# pcb.net
KiCad netlist of a schematic drawn in EAGLE
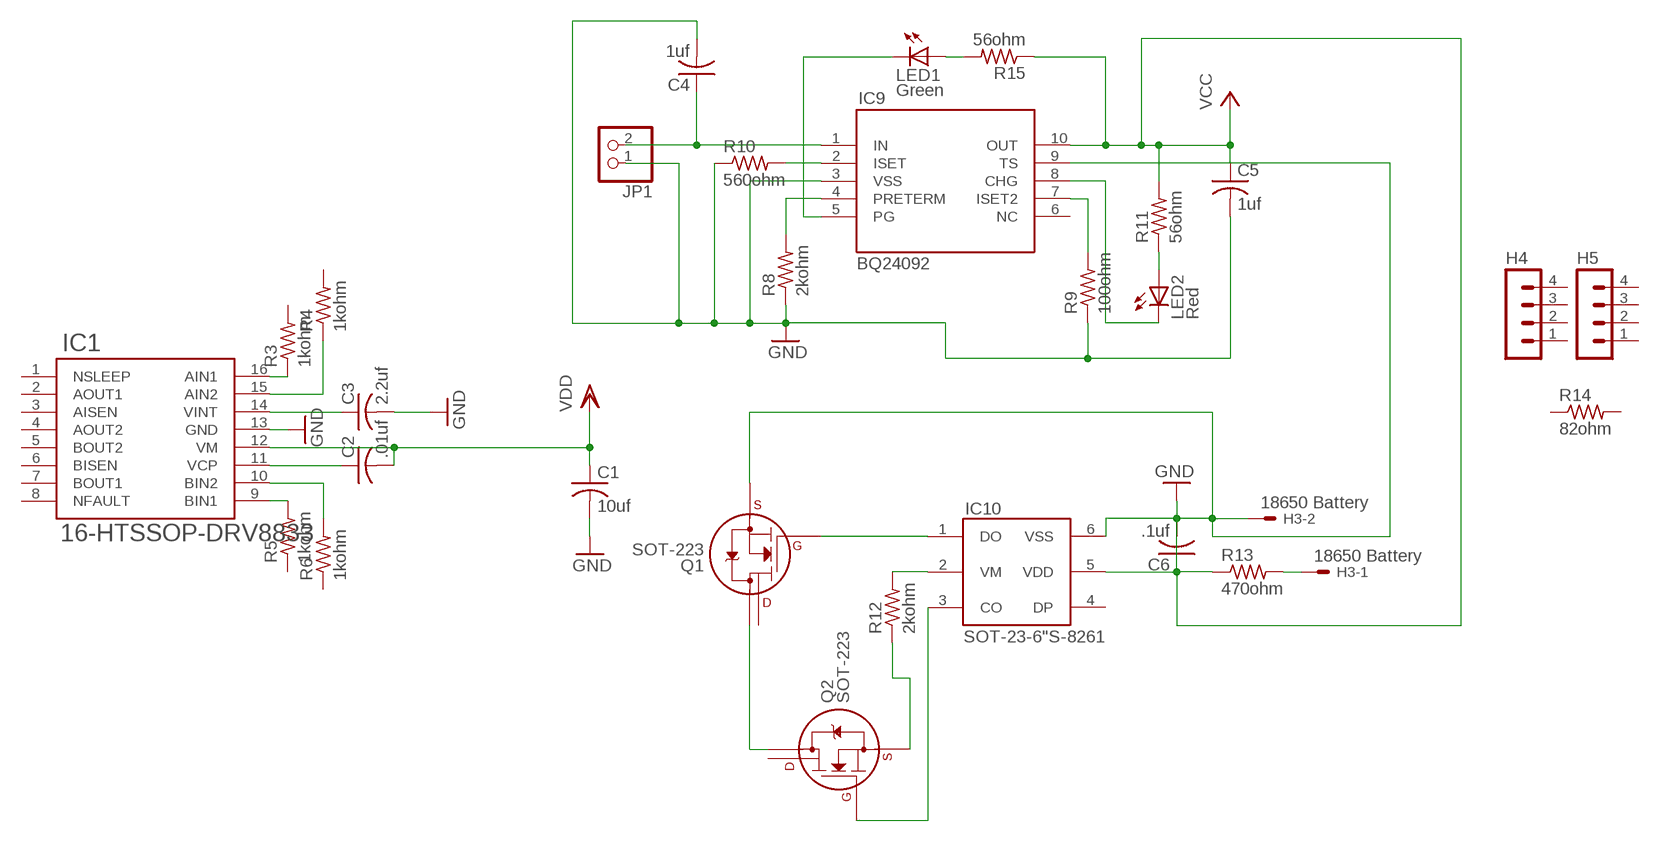
[diagram p0: schematic, sheet 1]

(export (version "E")
  (design (tool "Eeschema 10.0.6"))
  (components
    (comp (ref "C1")
      (value "10uf")
      (footprint "eagle-import:C0805")
      (libsource (lib "eagle-import") (part "C-USC0805"))
    )
    (comp (ref "C2")
      (value ".01uf")
      (footprint "eagle-import:C0805")
      (libsource (lib "eagle-import") (part "C-USC0805"))
    )
    (comp (ref "C3")
      (value "2.2uf")
      (footprint "eagle-import:C1206")
      (libsource (lib "eagle-import") (part "C-USC1206"))
    )
    (comp (ref "C4")
      (value "1uf")
      (footprint "eagle-import:C1206")
      (libsource (lib "eagle-import") (part "C-USC1206"))
    )
    (comp (ref "C5")
      (value "1uf")
      (footprint "eagle-import:C1206")
      (libsource (lib "eagle-import") (part "C-USC1206"))
    )
    (comp (ref "C6")
      (value ".1uf")
      (footprint "eagle-import:C1206")
      (libsource (lib "eagle-import") (part "C-USC1206"))
    )
    (comp (ref "H3")
      (value "18650 Battery")
      (footprint "eagle-import:KK-156-2")
      (libsource (lib "eagle-import") (part "KK-156-2"))
    )
    (comp (ref "H4")
      (value "MA04-1")
      (footprint "eagle-import:MA04-1")
      (libsource (lib "eagle-import") (part "MA04-1"))
    )
    (comp (ref "H5")
      (value "MA04-1")
      (footprint "eagle-import:MA04-1")
      (libsource (lib "eagle-import") (part "MA04-1"))
    )
    (comp (ref "IC1")
      (value "16-HTSSOP-DRV8833")
      (footprint "eagle-import:TSSOP16E")
      (libsource (lib "eagle-import") (part "16-HTSSOP-DRV8833"))
    )
    (comp (ref "IC9")
      (value "BQ24092")
      (footprint "eagle-import:DFN10-3X3")
      (libsource (lib "eagle-import") (part "BQ24092"))
    )
    (comp (ref "IC10")
      (value "SOT-23-6\"S-8261")
      (footprint "eagle-import:SOT23-6")
      (libsource (lib "eagle-import") (part "SOT-23-6{dblquote}S-8261"))
    )
    (comp (ref "JP1")
      (value "PINHD-1X2")
      (footprint "eagle-import:1X02")
      (libsource (lib "eagle-import") (part "PINHD-1X2"))
    )
    (comp (ref "LED1")
      (value "Green")
      (footprint "eagle-import:CHIPLED_0805")
      (libsource (lib "eagle-import") (part "LEDCHIPLED_0805"))
    )
    (comp (ref "LED2")
      (value "Red")
      (footprint "eagle-import:CHIPLED_0805")
      (libsource (lib "eagle-import") (part "LEDCHIPLED_0805"))
    )
    (comp (ref "Q1")
      (value "SOT-223")
      (footprint "eagle-import:SOT-223")
      (libsource (lib "eagle-import") (part "IRLL014"))
    )
    (comp (ref "Q2")
      (value "SOT-223")
      (footprint "eagle-import:SOT-223")
      (libsource (lib "eagle-import") (part "IRLL014"))
    )
    (comp (ref "R3")
      (value "1kohm")
      (footprint "eagle-import:R0805")
      (libsource (lib "eagle-import") (part "R-US_R0805"))
    )
    (comp (ref "R4")
      (value "1kohm")
      (footprint "eagle-import:R0805")
      (libsource (lib "eagle-import") (part "R-US_R0805"))
    )
    (comp (ref "R5")
      (value "1kohm")
      (footprint "eagle-import:R0805")
      (libsource (lib "eagle-import") (part "R-US_R0805"))
    )
    (comp (ref "R6")
      (value "1kohm")
      (footprint "eagle-import:R0805")
      (libsource (lib "eagle-import") (part "R-US_R0805"))
    )
    (comp (ref "R8")
      (value "2kohm")
      (footprint "eagle-import:R1206")
      (libsource (lib "eagle-import") (part "R-US_R1206"))
    )
    (comp (ref "R9")
      (value "100ohm")
      (footprint "eagle-import:R0805")
      (libsource (lib "eagle-import") (part "R-US_R0805"))
    )
    (comp (ref "R10")
      (value "560ohm")
      (footprint "eagle-import:R1206")
      (libsource (lib "eagle-import") (part "R-US_R1206"))
    )
    (comp (ref "R11")
      (value "56ohm")
      (footprint "eagle-import:R1206")
      (libsource (lib "eagle-import") (part "R-US_R1206"))
    )
    (comp (ref "R12")
      (value "2kohm")
      (footprint "eagle-import:R0805")
      (libsource (lib "eagle-import") (part "R-US_R0805"))
    )
    (comp (ref "R13")
      (value "470ohm")
      (footprint "eagle-import:R1206")
      (libsource (lib "eagle-import") (part "R-US_R1206"))
    )
    (comp (ref "R14")
      (value "82ohm")
      (footprint "eagle-import:R1206")
      (libsource (lib "eagle-import") (part "R-US_R1206"))
    )
    (comp (ref "R15")
      (value "56ohm")
      (footprint "eagle-import:R1206")
      (libsource (lib "eagle-import") (part "R-US_R1206"))
    )
  )
  (nets
    (net (code "1") (name "GND") (class "Default")
      (node (ref "C1") (pin "2") (pinfunction "2_2") (pintype "passive"))
      (node (ref "C3") (pin "2") (pinfunction "2_2") (pintype "passive"))
      (node (ref "C4") (pin "2") (pinfunction "2_2") (pintype "passive"))
      (node (ref "C5") (pin "1") (pinfunction "1_1") (pintype "passive"))
      (node (ref "C5") (pin "2") (pinfunction "2_2") (pintype "passive"))
      (node (ref "C6") (pin "1") (pinfunction "1_1") (pintype "passive"))
      (node (ref "C6") (pin "2") (pinfunction "2_2") (pintype "passive"))
      (node (ref "H3") (pin "2") (pinfunction "S_2") (pintype "passive"))
      (node (ref "IC1") (pin "13") (pinfunction "GND_13") (pintype "bidirectional"))
      (node (ref "IC10") (pin "5") (pinfunction "VDD_5") (pintype "bidirectional"))
      (node (ref "IC10") (pin "6") (pinfunction "VSS_6") (pintype "bidirectional"))
      (node (ref "IC9") (pin "10") (pinfunction "OUT_10") (pintype "bidirectional"))
      (node (ref "IC9") (pin "3") (pinfunction "VSS_3") (pintype "bidirectional"))
      (node (ref "IC9") (pin "9") (pinfunction "TS_9") (pintype "bidirectional"))
      (node (ref "JP1") (pin "1") (pinfunction "1_1") (pintype "passive"))
      (node (ref "Q1") (pin "3") (pinfunction "S_3") (pintype "bidirectional"))
      (node (ref "R10") (pin "1") (pinfunction "1_1") (pintype "passive"))
      (node (ref "R11") (pin "2") (pinfunction "2_2") (pintype "passive"))
      (node (ref "R13") (pin "1") (pinfunction "1_1") (pintype "passive"))
      (node (ref "R15") (pin "1") (pinfunction "1_1") (pintype "passive"))
      (node (ref "R8") (pin "1") (pinfunction "1_1") (pintype "passive"))
      (node (ref "R9") (pin "1") (pinfunction "1_1") (pintype "passive"))
    )
    (net (code "2") (name "Net-(H3A-S)") (class "Default")
      (node (ref "H3") (pin "1") (pinfunction "S_1") (pintype "passive"))
      (node (ref "R13") (pin "2") (pinfunction "2_2") (pintype "passive"))
    )
    (net (code "3") (name "Net-(IC1-AIN1)") (class "Default")
      (node (ref "IC1") (pin "16") (pinfunction "AIN1_16") (pintype "bidirectional"))
      (node (ref "R3") (pin "1") (pinfunction "1_1") (pintype "passive"))
    )
    (net (code "4") (name "Net-(IC1-AIN2)") (class "Default")
      (node (ref "IC1") (pin "15") (pinfunction "AIN2_15") (pintype "bidirectional"))
      (node (ref "R4") (pin "1") (pinfunction "1_1") (pintype "passive"))
    )
    (net (code "5") (name "Net-(IC1-BIN1)") (class "Default")
      (node (ref "IC1") (pin "9") (pinfunction "BIN1_9") (pintype "bidirectional"))
      (node (ref "R5") (pin "2") (pinfunction "2_2") (pintype "passive"))
    )
    (net (code "6") (name "Net-(IC1-BIN2)") (class "Default")
      (node (ref "IC1") (pin "10") (pinfunction "BIN2_10") (pintype "bidirectional"))
      (node (ref "R6") (pin "2") (pinfunction "2_2") (pintype "passive"))
    )
    (net (code "7") (name "Net-(IC1-VCP)") (class "Default")
      (node (ref "C2") (pin "1") (pinfunction "1_1") (pintype "passive"))
      (node (ref "IC1") (pin "11") (pinfunction "VCP_11") (pintype "bidirectional"))
    )
    (net (code "8") (name "Net-(IC1-VINT)") (class "Default")
      (node (ref "C3") (pin "1") (pinfunction "1_1") (pintype "passive"))
      (node (ref "IC1") (pin "14") (pinfunction "VINT_14") (pintype "bidirectional"))
    )
    (net (code "9") (name "Net-(IC9-CHG)") (class "Default")
      (node (ref "IC9") (pin "8") (pinfunction "CHG_8") (pintype "bidirectional"))
      (node (ref "LED2") (pin "C") (pinfunction "C_C") (pintype "passive"))
    )
    (net (code "10") (name "Net-(IC9-IN)") (class "Default")
      (node (ref "C4") (pin "1") (pinfunction "1_1") (pintype "passive"))
      (node (ref "IC9") (pin "1") (pinfunction "IN_1") (pintype "bidirectional"))
      (node (ref "JP1") (pin "2") (pinfunction "2_2") (pintype "passive"))
    )
    (net (code "11") (name "Net-(IC9-ISET)") (class "Default")
      (node (ref "IC9") (pin "2") (pinfunction "ISET_2") (pintype "bidirectional"))
      (node (ref "R10") (pin "2") (pinfunction "2_2") (pintype "passive"))
    )
    (net (code "12") (name "Net-(IC9-ISET2)") (class "Default")
      (node (ref "IC9") (pin "7") (pinfunction "ISET2_7") (pintype "bidirectional"))
      (node (ref "R9") (pin "2") (pinfunction "2_2") (pintype "passive"))
    )
    (net (code "13") (name "Net-(IC9-PG)") (class "Default")
      (node (ref "IC9") (pin "5") (pinfunction "PG_5") (pintype "bidirectional"))
      (node (ref "LED1") (pin "C") (pinfunction "C_C") (pintype "passive"))
    )
    (net (code "14") (name "Net-(IC9-PRETERM)") (class "Default")
      (node (ref "IC9") (pin "4") (pinfunction "PRETERM_4") (pintype "bidirectional"))
      (node (ref "R8") (pin "2") (pinfunction "2_2") (pintype "passive"))
    )
    (net (code "15") (name "Net-(IC10-CO)") (class "Default")
      (node (ref "IC10") (pin "3") (pinfunction "CO_3") (pintype "bidirectional"))
      (node (ref "Q2") (pin "1") (pinfunction "G_1") (pintype "tri_state"))
    )
    (net (code "16") (name "Net-(IC10-DO)") (class "Default")
      (node (ref "IC10") (pin "1") (pinfunction "DO_1") (pintype "bidirectional"))
      (node (ref "Q1") (pin "1") (pinfunction "G_1") (pintype "tri_state"))
    )
    (net (code "17") (name "Net-(IC10-VM)") (class "Default")
      (node (ref "IC10") (pin "2") (pinfunction "VM_2") (pintype "bidirectional"))
      (node (ref "R12") (pin "2") (pinfunction "2_2") (pintype "passive"))
    )
    (net (code "18") (name "Net-(LED1-PadA)") (class "Default")
      (node (ref "LED1") (pin "A") (pinfunction "A_A") (pintype "passive"))
      (node (ref "R15") (pin "2") (pinfunction "2_2") (pintype "passive"))
    )
    (net (code "19") (name "Net-(LED2-PadA)") (class "Default")
      (node (ref "LED2") (pin "A") (pinfunction "A_A") (pintype "passive"))
      (node (ref "R11") (pin "1") (pinfunction "1_1") (pintype "passive"))
    )
    (net (code "20") (name "Net-(Q1-D1)") (class "Default")
      (node (ref "Q1") (pin "2") (pinfunction "D1_2") (pintype "bidirectional"))
      (node (ref "Q2") (pin "2") (pinfunction "D1_2") (pintype "bidirectional"))
    )
    (net (code "21") (name "Net-(Q2-S)") (class "Default")
      (node (ref "Q2") (pin "3") (pinfunction "S_3") (pintype "bidirectional"))
      (node (ref "R12") (pin "1") (pinfunction "1_1") (pintype "passive"))
    )
    (net (code "22") (name "VDD") (class "Default")
      (node (ref "C1") (pin "1") (pinfunction "1_1") (pintype "passive"))
      (node (ref "C2") (pin "2") (pinfunction "2_2") (pintype "passive"))
      (node (ref "IC1") (pin "12") (pinfunction "VM_12") (pintype "bidirectional"))
    )
    (net (code "23") (name "unconnected-(H4-Pad1)") (class "Default")
      (node (ref "H4") (pin "1") (pinfunction "1_1") (pintype "passive"))
    )
    (net (code "24") (name "unconnected-(H4-Pad2)") (class "Default")
      (node (ref "H4") (pin "2") (pinfunction "2_2") (pintype "passive"))
    )
    (net (code "25") (name "unconnected-(H4-Pad3)") (class "Default")
      (node (ref "H4") (pin "3") (pinfunction "3_3") (pintype "passive"))
    )
    (net (code "26") (name "unconnected-(H4-Pad4)") (class "Default")
      (node (ref "H4") (pin "4") (pinfunction "4_4") (pintype "passive"))
    )
    (net (code "27") (name "unconnected-(H5-Pad1)") (class "Default")
      (node (ref "H5") (pin "1") (pinfunction "1_1") (pintype "passive"))
    )
    (net (code "28") (name "unconnected-(H5-Pad2)") (class "Default")
      (node (ref "H5") (pin "2") (pinfunction "2_2") (pintype "passive"))
    )
    (net (code "29") (name "unconnected-(H5-Pad3)") (class "Default")
      (node (ref "H5") (pin "3") (pinfunction "3_3") (pintype "passive"))
    )
    (net (code "30") (name "unconnected-(H5-Pad4)") (class "Default")
      (node (ref "H5") (pin "4") (pinfunction "4_4") (pintype "passive"))
    )
    (net (code "31") (name "unconnected-(IC1-AISEN-Pad3)") (class "Default")
      (node (ref "IC1") (pin "3") (pinfunction "AISEN_3") (pintype "bidirectional"))
    )
    (net (code "32") (name "unconnected-(IC1-AOUT1-Pad2)") (class "Default")
      (node (ref "IC1") (pin "2") (pinfunction "AOUT1_2") (pintype "bidirectional"))
    )
    (net (code "33") (name "unconnected-(IC1-AOUT2-Pad4)") (class "Default")
      (node (ref "IC1") (pin "4") (pinfunction "AOUT2_4") (pintype "bidirectional"))
    )
    (net (code "34") (name "unconnected-(IC1-BISEN-Pad6)") (class "Default")
      (node (ref "IC1") (pin "6") (pinfunction "BISEN_6") (pintype "bidirectional"))
    )
    (net (code "35") (name "unconnected-(IC1-BOUT1-Pad7)") (class "Default")
      (node (ref "IC1") (pin "7") (pinfunction "BOUT1_7") (pintype "bidirectional"))
    )
    (net (code "36") (name "unconnected-(IC1-BOUT2-Pad5)") (class "Default")
      (node (ref "IC1") (pin "5") (pinfunction "BOUT2_5") (pintype "bidirectional"))
    )
    (net (code "37") (name "unconnected-(IC1-NFAULT-Pad8)") (class "Default")
      (node (ref "IC1") (pin "8") (pinfunction "NFAULT_8") (pintype "bidirectional"))
    )
    (net (code "38") (name "unconnected-(IC1-NSLEEP-Pad1)") (class "Default")
      (node (ref "IC1") (pin "1") (pinfunction "NSLEEP_1") (pintype "bidirectional"))
    )
    (net (code "39") (name "unconnected-(IC9-NC-Pad6)") (class "Default")
      (node (ref "IC9") (pin "6") (pinfunction "NC_6") (pintype "bidirectional"))
    )
    (net (code "40") (name "unconnected-(IC10-DP-Pad4)") (class "Default")
      (node (ref "IC10") (pin "4") (pinfunction "DP_4") (pintype "bidirectional"))
    )
    (net (code "41") (name "unconnected-(Q1-D2-Pad4)") (class "Default")
      (node (ref "Q1") (pin "4") (pinfunction "D2_4") (pintype "bidirectional"))
    )
    (net (code "42") (name "unconnected-(Q2-D2-Pad4)") (class "Default")
      (node (ref "Q2") (pin "4") (pinfunction "D2_4") (pintype "bidirectional"))
    )
    (net (code "43") (name "unconnected-(R3-Pad2)") (class "Default")
      (node (ref "R3") (pin "2") (pinfunction "2_2") (pintype "passive"))
    )
    (net (code "44") (name "unconnected-(R4-Pad2)") (class "Default")
      (node (ref "R4") (pin "2") (pinfunction "2_2") (pintype "passive"))
    )
    (net (code "45") (name "unconnected-(R5-Pad1)") (class "Default")
      (node (ref "R5") (pin "1") (pinfunction "1_1") (pintype "passive"))
    )
    (net (code "46") (name "unconnected-(R6-Pad1)") (class "Default")
      (node (ref "R6") (pin "1") (pinfunction "1_1") (pintype "passive"))
    )
    (net (code "47") (name "unconnected-(R14-Pad1)") (class "Default")
      (node (ref "R14") (pin "1") (pinfunction "1_1") (pintype "passive"))
    )
    (net (code "48") (name "unconnected-(R14-Pad2)") (class "Default")
      (node (ref "R14") (pin "2") (pinfunction "2_2") (pintype "passive"))
    )
  )
)
